# STM32G4.net
KiCad netlist of a schematic drawn in Altium Designer
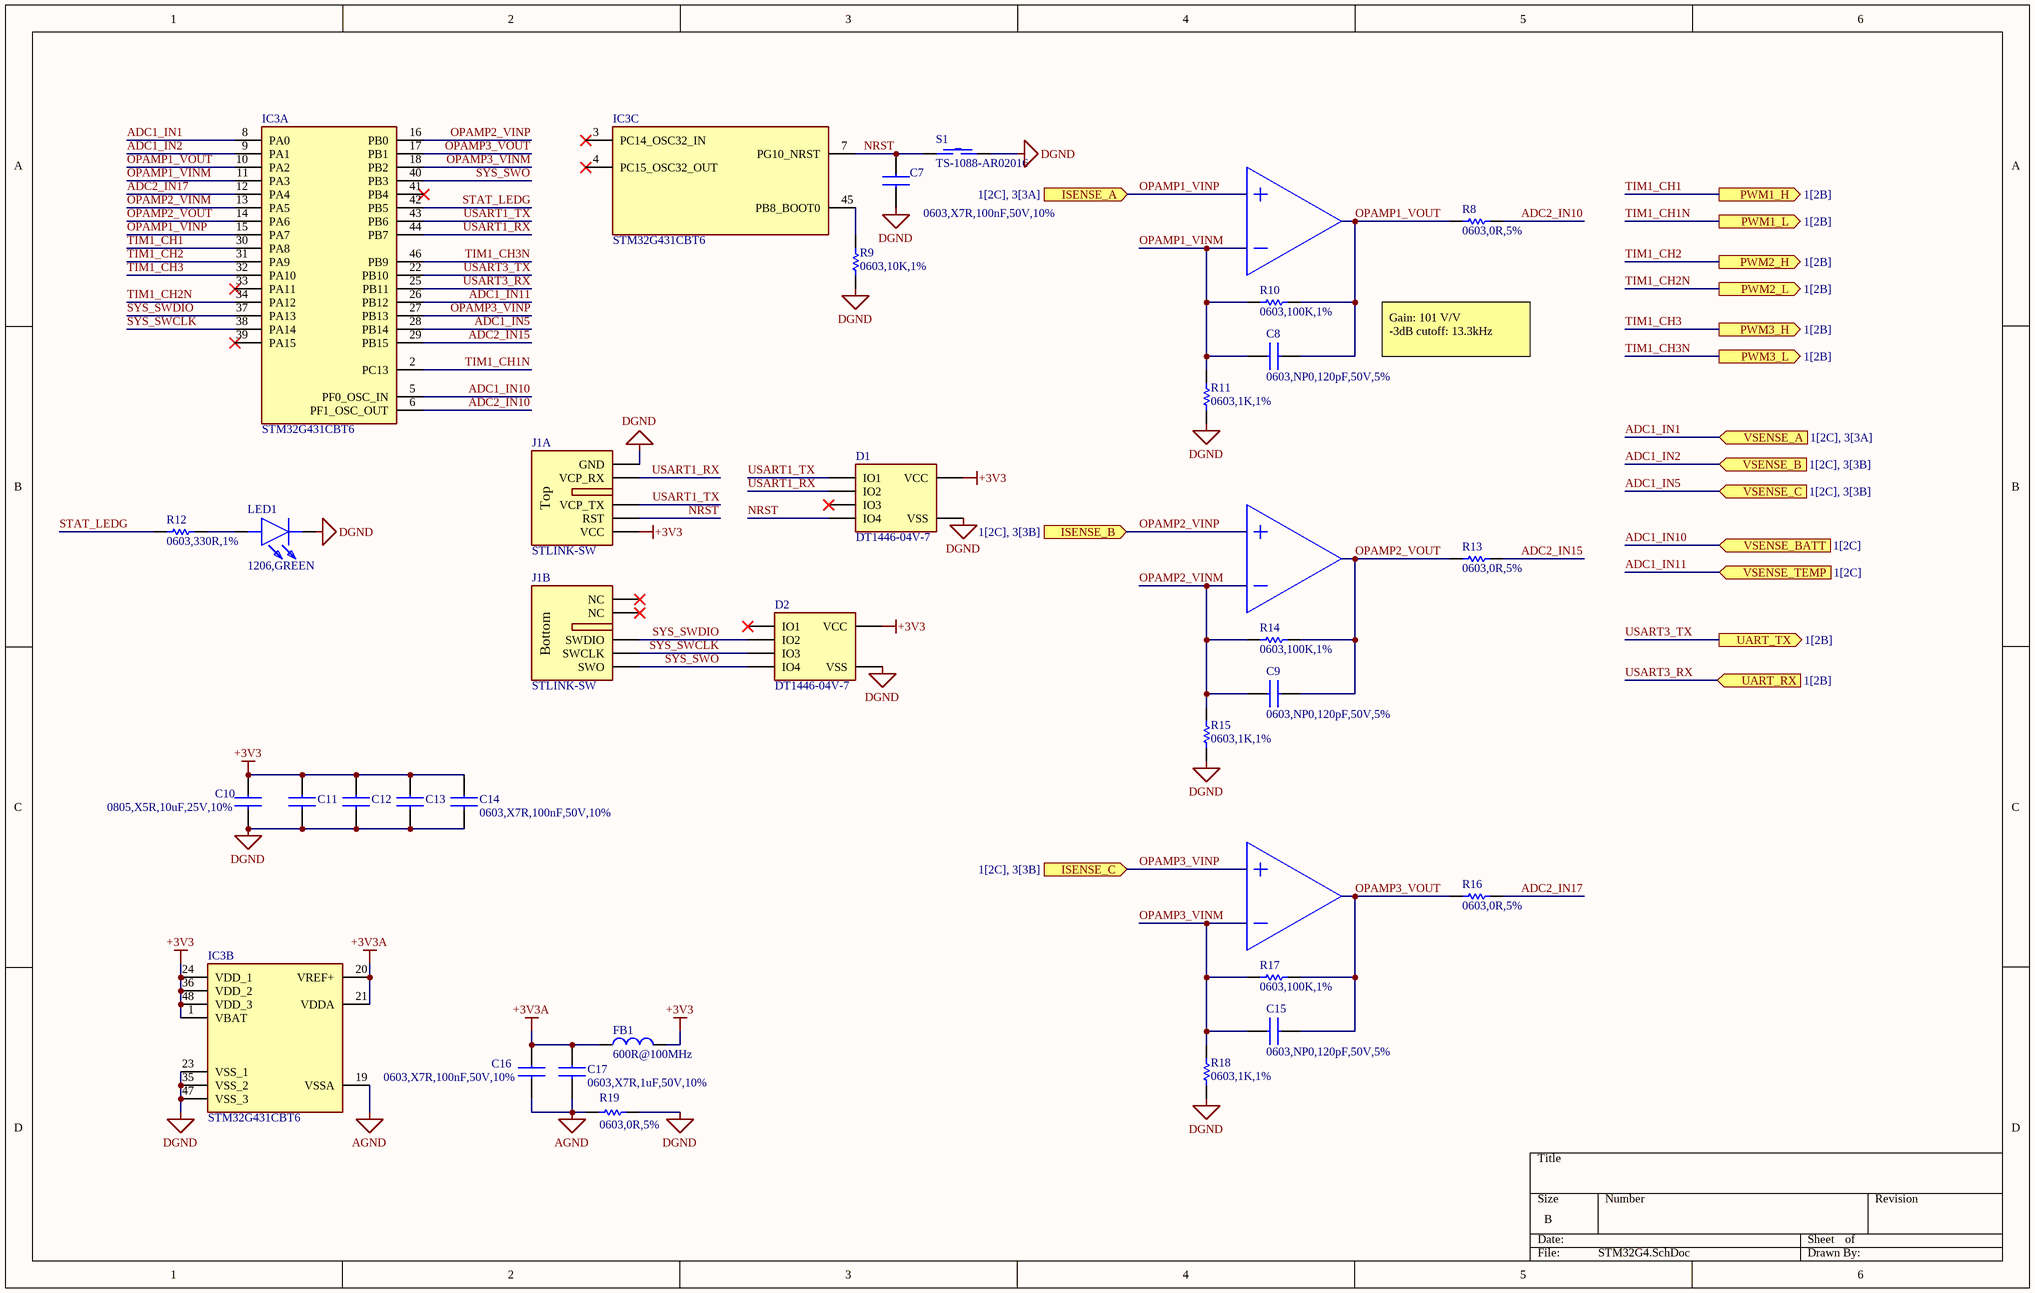
[diagram p0: STM32G4.SchDoc]

(export (version "E")
  (design (tool "Eeschema 10.0.6"))
  (components
    (comp (ref "C7")
      (value "0603,X7R,100nF,50V,10%")
      (footprint "CAPC1608X90N")
      (description "50V 100nF X7R ±10% 0603 Multilayer Ceramic Capacitors MLCC - SMD/SMT ROHS")
      (fields
        (field (name "MANUFACTURER_PART_NUMBER") "CC0603KRX7R9BB104")
        (field (name "MOUSER PART NUMBER") "603-CC603KRX7R9BB104")
      )
      (libsource (lib "ESC") (part "CC0603KRX7R9BB104"))
    )
    (comp (ref "C8")
      (value "0603,NP0,120pF,50V,5%")
      (footprint "CAPC1608X90N")
      (description "50V 120pF NP0 ±5% 0603 Multilayer Ceramic Capacitors MLCC - SMD/SMT ROHS")
      (fields
        (field (name "MANUFACTURER_PART_NUMBER") "CC0603JRNPO9BN121")
        (field (name "MOUSER PART NUMBER") "603-CC603KRX7R9BB104")
      )
      (libsource (lib "ESC") (part "CC0603JRNPO9BN121"))
    )
    (comp (ref "C9")
      (value "0603,NP0,120pF,50V,5%")
      (footprint "CAPC1608X90N")
      (description "50V 120pF NP0 ±5% 0603 Multilayer Ceramic Capacitors MLCC - SMD/SMT ROHS")
      (fields
        (field (name "MANUFACTURER_PART_NUMBER") "CC0603JRNPO9BN121")
        (field (name "MOUSER PART NUMBER") "603-CC603KRX7R9BB104")
      )
      (libsource (lib "ESC") (part "CC0603JRNPO9BN121"))
    )
    (comp (ref "C10")
      (value "0805,X5R,10uF,25V,10%")
      (footprint "CAPC2012X145N")
      (description "10 µF ±10% 25V Ceramic Capacitor X5R 0805 (2012 Metric)")
      (fields
        (field (name "MANUFACTURER_PART_NUMBER") "CC0805KKX5R8BB106")
        (field (name "MOUSER PART NUMBER") "603-CC805KKX5R8BB106")
      )
      (libsource (lib "ESC") (part "CC0805KKX5R8BB106"))
    )
    (comp (ref "C11")
      (value "0603,X7R,100nF,50V,10%")
      (footprint "CAPC1608X90N")
      (description "50V 100nF X7R ±10% 0603 Multilayer Ceramic Capacitors MLCC - SMD/SMT ROHS")
      (fields
        (field (name "MANUFACTURER_PART_NUMBER") "CC0603KRX7R9BB104")
        (field (name "MOUSER PART NUMBER") "603-CC603KRX7R9BB104")
      )
      (libsource (lib "ESC") (part "CC0603KRX7R9BB104"))
    )
    (comp (ref "C12")
      (value "0603,X7R,100nF,50V,10%")
      (footprint "CAPC1608X90N")
      (description "50V 100nF X7R ±10% 0603 Multilayer Ceramic Capacitors MLCC - SMD/SMT ROHS")
      (fields
        (field (name "MANUFACTURER_PART_NUMBER") "CC0603KRX7R9BB104")
        (field (name "MOUSER PART NUMBER") "603-CC603KRX7R9BB104")
      )
      (libsource (lib "ESC") (part "CC0603KRX7R9BB104"))
    )
    (comp (ref "C13")
      (value "0603,X7R,100nF,50V,10%")
      (footprint "CAPC1608X90N")
      (description "50V 100nF X7R ±10% 0603 Multilayer Ceramic Capacitors MLCC - SMD/SMT ROHS")
      (fields
        (field (name "MANUFACTURER_PART_NUMBER") "CC0603KRX7R9BB104")
        (field (name "MOUSER PART NUMBER") "603-CC603KRX7R9BB104")
      )
      (libsource (lib "ESC") (part "CC0603KRX7R9BB104"))
    )
    (comp (ref "C14")
      (value "0603,X7R,100nF,50V,10%")
      (footprint "CAPC1608X90N")
      (description "50V 100nF X7R ±10% 0603 Multilayer Ceramic Capacitors MLCC - SMD/SMT ROHS")
      (fields
        (field (name "MANUFACTURER_PART_NUMBER") "CC0603KRX7R9BB104")
        (field (name "MOUSER PART NUMBER") "603-CC603KRX7R9BB104")
      )
      (libsource (lib "ESC") (part "CC0603KRX7R9BB104"))
    )
    (comp (ref "C15")
      (value "0603,NP0,120pF,50V,5%")
      (footprint "CAPC1608X90N")
      (description "50V 120pF NP0 ±5% 0603 Multilayer Ceramic Capacitors MLCC - SMD/SMT ROHS")
      (fields
        (field (name "MANUFACTURER_PART_NUMBER") "CC0603JRNPO9BN121")
        (field (name "MOUSER PART NUMBER") "603-CC603KRX7R9BB104")
      )
      (libsource (lib "ESC") (part "CC0603JRNPO9BN121"))
    )
    (comp (ref "C16")
      (value "0603,X7R,100nF,50V,10%")
      (footprint "CAPC1608X90N")
      (description "50V 100nF X7R ±10% 0603 Multilayer Ceramic Capacitors MLCC - SMD/SMT ROHS")
      (fields
        (field (name "MANUFACTURER_PART_NUMBER") "CC0603KRX7R9BB104")
        (field (name "MOUSER PART NUMBER") "603-CC603KRX7R9BB104")
      )
      (libsource (lib "ESC") (part "CC0603KRX7R9BB104"))
    )
    (comp (ref "C17")
      (value "0603,X7R,1uF,50V,10%")
      (footprint "CAPC1608X90N")
      (description "50V 1uF X7R ±10% 0603 Multilayer Ceramic Capacitors MLCC - SMD/SMT ROHS")
      (fields
        (field (name "MANUFACTURER_PART_NUMBER") "CC0603KRX7R9BB105")
        (field (name "MOUSER PART NUMBER") "603-CC603KRX7R9BB105")
      )
      (libsource (lib "ESC") (part "CC0603KRX7R9BB105"))
    )
    (comp (ref "D1")
      (value "DT1446-04V-7")
      (footprint "SOTFL50P162X60-6N")
      (description "8.5V Clamp 4.7A (8/20µs) Ipp Tvs Diode Surface Mount SOT-563")
      (fields (field (name "MOUSER PART NUMBER") "621-DT1446-04V-7") (field (name "LCSC PART #") "C460066"))
      (libsource (lib "ESC") (part "DT1446-04V-7"))
    )
    (comp (ref "D2")
      (value "DT1446-04V-7")
      (footprint "SOTFL50P162X60-6N")
      (description "8.5V Clamp 4.7A (8/20µs) Ipp Tvs Diode Surface Mount SOT-563")
      (fields (field (name "MOUSER PART NUMBER") "621-DT1446-04V-7") (field (name "LCSC PART #") "C460066"))
      (libsource (lib "ESC") (part "DT1446-04V-7"))
    )
    (comp (ref "FB1")
      (value "600R@100MHz")
      (footprint "L0603")
      (description "380mΩ ±25% 600Ω@100MHz 0603 Ferrite Beads ROHS")
      (fields (field (name "LCSC PART #") "C19330"))
      (libsource (lib "ESC") (part "BLM18AG601SN1D"))
    )
    (comp (ref "IC3")
      (value "STM32G431CBT6")
      (footprint "QFP50P900X900X160-48N")
      (fields (field (name "MOUSER PART NUMBER") "511-STM32G431CBT6") (field (name "LCSC PART #") "C529355"))
      (libsource (lib "ESC") (part "STM32G431CBT6"))
    )
    (comp (ref "J1")
      (value "STLINK-SW")
      (footprint "Valkyrie ESC:009159010061911")
      (description "SSL Connector 10 Position Adapter, Bridge Board to Board - Card Edge 0.079\" (2.00mm)")
      (libsource (lib "ESC") (part "STLINK-SW"))
    )
    (comp (ref "LED1")
      (value "1206,GREEN")
      (footprint "LEDC3216X120N")
      (fields
        (field (name "MANUFACTURER_PART_NUMBER") "LTST-C150KGKT")
        (field (name "MOUSER PART NUMBER") "859-LTST-C150KGKT")
        (field (name "LCSC PART #") "C125085")
      )
      (libsource (lib "ESC") (part "LTST-C150KGKT"))
    )
    (comp (ref "R8")
      (value "0603,0R,5%")
      (footprint "RESC1608X55N")
      (description "100mW Thick Film Resistor 75V ±5% 0Ω 0603 Chip Resistor - Surface Mount ROHS")
      (fields
        (field (name "MANUFACTURER_PART_NUMBER") "RC0603JR-070RL")
        (field (name "LCSC PART #") "C95177")
      )
      (libsource (lib "ESC") (part "RC0603JR-070RL"))
    )
    (comp (ref "R9")
      (value "0603,10K,1%")
      (footprint "RESC1608X55N")
      (description "100mW 10kΩ 75V ±100ppm/℃ Thick Film Resistor ±1% 0603 Chip Resistor - Surface Mount RoHS")
      (fields
        (field (name "MANUFACTURER_PART_NUMBER") "RC0603FR-0710KL")
        (field (name "LCSC PART #") "C98220")
      )
      (libsource (lib "ESC") (part "RC0603FR-0710KL"))
    )
    (comp (ref "R10")
      (value "0603,100K,1%")
      (footprint "RESC1608X55N")
      (description "100mW Thick Film Resistor 75V ±100ppm/℃ ±1% 100kΩ 0603 Chip Resistor - Surface Mount ROHS")
      (fields
        (field (name "MANUFACTURER_PART_NUMBER") "RC0603FR-07100KL")
        (field (name "LCSC PART #") "C14675")
      )
      (libsource (lib "ESC") (part "RC0603FR-07100KL"))
    )
    (comp (ref "R11")
      (value "0603,1K,1%")
      (footprint "RESC1608X55N")
      (description "100mW Thick Film Resistor 75V ±100ppm/℃ ±1% 1kΩ 0603 Chip Resistor - Surface Mount ROHS")
      (fields
        (field (name "MANUFACTURER_PART_NUMBER") "RC0603FR-071KL")
        (field (name "LCSC PART #") "C22548")
      )
      (libsource (lib "ESC") (part "RC0603FR-071KL"))
    )
    (comp (ref "R12")
      (value "0603,330R,1%")
      (footprint "RESC1608X55N")
      (description "100mW 330Ω 75V ±100ppm/℃ Thick Film Resistor ±1% 0603 Chip Resistor - Surface Mount RoHS")
      (fields
        (field (name "MANUFACTURER_PART_NUMBER") "RC0603FR-07330RL")
        (field (name "LCSC PART #") "C105881")
      )
      (libsource (lib "ESC") (part "RC0603FR-07330RL"))
    )
    (comp (ref "R13")
      (value "0603,0R,5%")
      (footprint "RESC1608X55N")
      (description "100mW Thick Film Resistor 75V ±5% 0Ω 0603 Chip Resistor - Surface Mount ROHS")
      (fields
        (field (name "MANUFACTURER_PART_NUMBER") "RC0603JR-070RL")
        (field (name "LCSC PART #") "C95177")
      )
      (libsource (lib "ESC") (part "RC0603JR-070RL"))
    )
    (comp (ref "R14")
      (value "0603,100K,1%")
      (footprint "RESC1608X55N")
      (description "100mW Thick Film Resistor 75V ±100ppm/℃ ±1% 100kΩ 0603 Chip Resistor - Surface Mount ROHS")
      (fields
        (field (name "MANUFACTURER_PART_NUMBER") "RC0603FR-07100KL")
        (field (name "LCSC PART #") "C14675")
      )
      (libsource (lib "ESC") (part "RC0603FR-07100KL"))
    )
    (comp (ref "R15")
      (value "0603,1K,1%")
      (footprint "RESC1608X55N")
      (description "100mW Thick Film Resistor 75V ±100ppm/℃ ±1% 1kΩ 0603 Chip Resistor - Surface Mount ROHS")
      (fields
        (field (name "MANUFACTURER_PART_NUMBER") "RC0603FR-071KL")
        (field (name "LCSC PART #") "C22548")
      )
      (libsource (lib "ESC") (part "RC0603FR-071KL"))
    )
    (comp (ref "R16")
      (value "0603,0R,5%")
      (footprint "RESC1608X55N")
      (description "100mW Thick Film Resistor 75V ±5% 0Ω 0603 Chip Resistor - Surface Mount ROHS")
      (fields
        (field (name "MANUFACTURER_PART_NUMBER") "RC0603JR-070RL")
        (field (name "LCSC PART #") "C95177")
      )
      (libsource (lib "ESC") (part "RC0603JR-070RL"))
    )
    (comp (ref "R17")
      (value "0603,100K,1%")
      (footprint "RESC1608X55N")
      (description "100mW Thick Film Resistor 75V ±100ppm/℃ ±1% 100kΩ 0603 Chip Resistor - Surface Mount ROHS")
      (fields
        (field (name "MANUFACTURER_PART_NUMBER") "RC0603FR-07100KL")
        (field (name "LCSC PART #") "C14675")
      )
      (libsource (lib "ESC") (part "RC0603FR-07100KL"))
    )
    (comp (ref "R18")
      (value "0603,1K,1%")
      (footprint "RESC1608X55N")
      (description "100mW Thick Film Resistor 75V ±100ppm/℃ ±1% 1kΩ 0603 Chip Resistor - Surface Mount ROHS")
      (fields
        (field (name "MANUFACTURER_PART_NUMBER") "RC0603FR-071KL")
        (field (name "LCSC PART #") "C22548")
      )
      (libsource (lib "ESC") (part "RC0603FR-071KL"))
    )
    (comp (ref "R19")
      (value "0603,0R,5%")
      (footprint "RESC1608X55N")
      (description "100mW Thick Film Resistor 75V ±5% 0Ω 0603 Chip Resistor - Surface Mount ROHS")
      (fields
        (field (name "MANUFACTURER_PART_NUMBER") "RC0603JR-070RL")
        (field (name "LCSC PART #") "C95177")
      )
      (libsource (lib "ESC") (part "RC0603JR-070RL"))
    )
    (comp (ref "S1")
      (value "TS-1088-AR02016")
      (footprint "SW-SMD_L3.9-W3.0-P4.45")
      (fields (field (name "LCSC PART #") "C720477"))
      (libsource (lib "ESC") (part "TS-1088-AR02016"))
    )
  )
  (nets
    (net (code "1") (name "+3V3") (class "Default")
      (node (ref "C10") (pin "2") (pinfunction "2_2") (pintype "passive"))
      (node (ref "C11") (pin "2") (pinfunction "2_2") (pintype "passive"))
      (node (ref "C12") (pin "2") (pinfunction "2_2") (pintype "passive"))
      (node (ref "C13") (pin "2") (pinfunction "2_2") (pintype "passive"))
      (node (ref "C14") (pin "2") (pinfunction "2_2") (pintype "passive"))
      (node (ref "D1") (pin "5") (pinfunction "VCC_5") (pintype "passive"))
      (node (ref "D2") (pin "5") (pinfunction "VCC_5") (pintype "passive"))
      (node (ref "FB1") (pin "2") (pinfunction "2_2") (pintype "passive"))
      (node (ref "IC3") (pin "1") (pinfunction "VBAT_1") (pintype "passive"))
      (node (ref "IC3") (pin "24") (pinfunction "VDD_1_24") (pintype "passive"))
      (node (ref "IC3") (pin "36") (pinfunction "VDD_2_36") (pintype "passive"))
      (node (ref "IC3") (pin "48") (pinfunction "VDD_3_48") (pintype "passive"))
      (node (ref "J1") (pin "5") (pinfunction "VCC_5") (pintype "passive"))
    )
    (net (code "2") (name "+3V3A") (class "Default")
      (node (ref "C16") (pin "2") (pinfunction "2_2") (pintype "passive"))
      (node (ref "C17") (pin "2") (pinfunction "2_2") (pintype "passive"))
      (node (ref "FB1") (pin "1") (pinfunction "1_1") (pintype "passive"))
      (node (ref "IC3") (pin "20") (pinfunction "VREF+_20") (pintype "passive"))
      (node (ref "IC3") (pin "21") (pinfunction "VDDA_21") (pintype "passive"))
    )
    (net (code "3") (name "/ADC1_IN1") (class "Default")
      (node (ref "IC3") (pin "8") (pinfunction "PA0_8") (pintype "passive"))
    )
    (net (code "4") (name "/ADC1_IN2") (class "Default")
      (node (ref "IC3") (pin "9") (pinfunction "PA1_9") (pintype "passive"))
    )
    (net (code "5") (name "/ADC1_IN5") (class "Default")
      (node (ref "IC3") (pin "28") (pinfunction "PB14_28") (pintype "passive"))
    )
    (net (code "6") (name "/ADC1_IN10") (class "Default")
      (node (ref "IC3") (pin "5") (pinfunction "PF0_OSC_IN_5") (pintype "passive"))
    )
    (net (code "7") (name "/ADC1_IN11") (class "Default")
      (node (ref "IC3") (pin "26") (pinfunction "PB12_26") (pintype "passive"))
    )
    (net (code "8") (name "/ADC2_IN10") (class "Default")
      (node (ref "IC3") (pin "6") (pinfunction "PF1_OSC_OUT_6") (pintype "passive"))
      (node (ref "R8") (pin "2") (pinfunction "2_2") (pintype "passive"))
    )
    (net (code "9") (name "/ADC2_IN15") (class "Default")
      (node (ref "IC3") (pin "29") (pinfunction "PB15_29") (pintype "passive"))
      (node (ref "R13") (pin "2") (pinfunction "2_2") (pintype "passive"))
    )
    (net (code "10") (name "/ADC2_IN17") (class "Default")
      (node (ref "IC3") (pin "12") (pinfunction "PA4_12") (pintype "passive"))
      (node (ref "R16") (pin "2") (pinfunction "2_2") (pintype "passive"))
    )
    (net (code "11") (name "/NRST") (class "Default")
      (node (ref "C7") (pin "2") (pinfunction "2_2") (pintype "passive"))
      (node (ref "D1") (pin "6") (pinfunction "IO4_6") (pintype "passive"))
      (node (ref "IC3") (pin "7") (pinfunction "PG10_NRST_7") (pintype "passive"))
      (node (ref "J1") (pin "4") (pinfunction "RST_4") (pintype "passive"))
      (node (ref "S1") (pin "2") (pinfunction "2_2") (pintype "passive"))
    )
    (net (code "12") (name "/OPAMP1_VINM") (class "Default")
      (node (ref "C8") (pin "1") (pinfunction "1_1") (pintype "passive"))
      (node (ref "IC3") (pin "11") (pinfunction "PA3_11") (pintype "passive"))
      (node (ref "R10") (pin "1") (pinfunction "1_1") (pintype "passive"))
      (node (ref "R11") (pin "2") (pinfunction "2_2") (pintype "passive"))
    )
    (net (code "13") (name "/OPAMP1_VINP") (class "Default")
      (node (ref "IC3") (pin "15") (pinfunction "PA7_15") (pintype "passive"))
    )
    (net (code "14") (name "/OPAMP1_VOUT") (class "Default")
      (node (ref "C8") (pin "2") (pinfunction "2_2") (pintype "passive"))
      (node (ref "IC3") (pin "10") (pinfunction "PA2_10") (pintype "passive"))
      (node (ref "R10") (pin "2") (pinfunction "2_2") (pintype "passive"))
      (node (ref "R8") (pin "1") (pinfunction "1_1") (pintype "passive"))
    )
    (net (code "15") (name "/OPAMP2_VINM") (class "Default")
      (node (ref "C9") (pin "1") (pinfunction "1_1") (pintype "passive"))
      (node (ref "IC3") (pin "13") (pinfunction "PA5_13") (pintype "passive"))
      (node (ref "R14") (pin "1") (pinfunction "1_1") (pintype "passive"))
      (node (ref "R15") (pin "2") (pinfunction "2_2") (pintype "passive"))
    )
    (net (code "16") (name "/OPAMP2_VINP") (class "Default")
      (node (ref "IC3") (pin "16") (pinfunction "PB0_16") (pintype "passive"))
    )
    (net (code "17") (name "/OPAMP2_VOUT") (class "Default")
      (node (ref "C9") (pin "2") (pinfunction "2_2") (pintype "passive"))
      (node (ref "IC3") (pin "14") (pinfunction "PA6_14") (pintype "passive"))
      (node (ref "R13") (pin "1") (pinfunction "1_1") (pintype "passive"))
      (node (ref "R14") (pin "2") (pinfunction "2_2") (pintype "passive"))
    )
    (net (code "18") (name "/OPAMP3_VINM") (class "Default")
      (node (ref "C15") (pin "1") (pinfunction "1_1") (pintype "passive"))
      (node (ref "IC3") (pin "18") (pinfunction "PB2_18") (pintype "passive"))
      (node (ref "R17") (pin "1") (pinfunction "1_1") (pintype "passive"))
      (node (ref "R18") (pin "2") (pinfunction "2_2") (pintype "passive"))
    )
    (net (code "19") (name "/OPAMP3_VINP") (class "Default")
      (node (ref "IC3") (pin "27") (pinfunction "PB13_27") (pintype "passive"))
    )
    (net (code "20") (name "/OPAMP3_VOUT") (class "Default")
      (node (ref "C15") (pin "2") (pinfunction "2_2") (pintype "passive"))
      (node (ref "IC3") (pin "17") (pinfunction "PB1_17") (pintype "passive"))
      (node (ref "R16") (pin "1") (pinfunction "1_1") (pintype "passive"))
      (node (ref "R17") (pin "2") (pinfunction "2_2") (pintype "passive"))
    )
    (net (code "21") (name "/STAT_LEDG") (class "Default")
      (node (ref "IC3") (pin "42") (pinfunction "PB5_42") (pintype "passive"))
      (node (ref "R12") (pin "1") (pinfunction "1_1") (pintype "passive"))
    )
    (net (code "22") (name "/SYS_SWCLK") (class "Default")
      (node (ref "D2") (pin "4") (pinfunction "IO3_4") (pintype "passive"))
      (node (ref "IC3") (pin "38") (pinfunction "PA14_38") (pintype "passive"))
      (node (ref "J1") (pin "9") (pinfunction "SWCLK_9") (pintype "passive"))
    )
    (net (code "23") (name "/SYS_SWDIO") (class "Default")
      (node (ref "D2") (pin "3") (pinfunction "IO2_3") (pintype "passive"))
      (node (ref "IC3") (pin "37") (pinfunction "PA13_37") (pintype "passive"))
      (node (ref "J1") (pin "8") (pinfunction "SWDIO_8") (pintype "passive"))
    )
    (net (code "24") (name "/SYS_SWO") (class "Default")
      (node (ref "D2") (pin "6") (pinfunction "IO4_6") (pintype "passive"))
      (node (ref "IC3") (pin "40") (pinfunction "PB3_40") (pintype "passive"))
      (node (ref "J1") (pin "10") (pinfunction "SWO_10") (pintype "passive"))
    )
    (net (code "25") (name "/TIM1_CH1") (class "Default")
      (node (ref "IC3") (pin "30") (pinfunction "PA8_30") (pintype "passive"))
    )
    (net (code "26") (name "/TIM1_CH1N") (class "Default")
      (node (ref "IC3") (pin "2") (pinfunction "PC13_2") (pintype "passive"))
    )
    (net (code "27") (name "/TIM1_CH2") (class "Default")
      (node (ref "IC3") (pin "31") (pinfunction "PA9_31") (pintype "passive"))
    )
    (net (code "28") (name "/TIM1_CH2N") (class "Default")
      (node (ref "IC3") (pin "34") (pinfunction "PA12_34") (pintype "passive"))
    )
    (net (code "29") (name "/TIM1_CH3") (class "Default")
      (node (ref "IC3") (pin "32") (pinfunction "PA10_32") (pintype "passive"))
    )
    (net (code "30") (name "/TIM1_CH3N") (class "Default")
      (node (ref "IC3") (pin "46") (pinfunction "PB9_46") (pintype "passive"))
    )
    (net (code "31") (name "/USART1_RX") (class "Default")
      (node (ref "D1") (pin "3") (pinfunction "IO2_3") (pintype "passive"))
      (node (ref "IC3") (pin "44") (pinfunction "PB7_44") (pintype "passive"))
      (node (ref "J1") (pin "2") (pinfunction "VCP_RX_2") (pintype "passive"))
    )
    (net (code "32") (name "/USART1_TX") (class "Default")
      (node (ref "D1") (pin "1") (pinfunction "IO1_1") (pintype "passive"))
      (node (ref "IC3") (pin "43") (pinfunction "PB6_43") (pintype "passive"))
      (node (ref "J1") (pin "3") (pinfunction "VCP_TX_3") (pintype "passive"))
    )
    (net (code "33") (name "/USART3_RX") (class "Default")
      (node (ref "IC3") (pin "25") (pinfunction "PB11_25") (pintype "passive"))
    )
    (net (code "34") (name "/USART3_TX") (class "Default")
      (node (ref "IC3") (pin "22") (pinfunction "PB10_22") (pintype "passive"))
    )
    (net (code "35") (name "AGND") (class "Default")
      (node (ref "C16") (pin "1") (pinfunction "1_1") (pintype "passive"))
      (node (ref "C17") (pin "1") (pinfunction "1_1") (pintype "passive"))
      (node (ref "IC3") (pin "19") (pinfunction "VSSA_19") (pintype "passive"))
      (node (ref "R19") (pin "1") (pinfunction "1_1") (pintype "passive"))
    )
    (net (code "36") (name "DGND") (class "Default")
      (node (ref "C10") (pin "1") (pinfunction "1_1") (pintype "passive"))
      (node (ref "C11") (pin "1") (pinfunction "1_1") (pintype "passive"))
      (node (ref "C12") (pin "1") (pinfunction "1_1") (pintype "passive"))
      (node (ref "C13") (pin "1") (pinfunction "1_1") (pintype "passive"))
      (node (ref "C14") (pin "1") (pinfunction "1_1") (pintype "passive"))
      (node (ref "C7") (pin "1") (pinfunction "1_1") (pintype "passive"))
      (node (ref "D1") (pin "2") (pinfunction "VSS_2") (pintype "passive"))
      (node (ref "D2") (pin "2") (pinfunction "VSS_2") (pintype "passive"))
      (node (ref "IC3") (pin "23") (pinfunction "VSS_1_23") (pintype "passive"))
      (node (ref "IC3") (pin "35") (pinfunction "VSS_2_35") (pintype "passive"))
      (node (ref "IC3") (pin "47") (pinfunction "VSS_3_47") (pintype "passive"))
      (node (ref "J1") (pin "1") (pinfunction "GND_1") (pintype "passive"))
      (node (ref "LED1") (pin "1") (pinfunction "K_1") (pintype "passive"))
      (node (ref "R11") (pin "1") (pinfunction "1_1") (pintype "passive"))
      (node (ref "R15") (pin "1") (pinfunction "1_1") (pintype "passive"))
      (node (ref "R18") (pin "1") (pinfunction "1_1") (pintype "passive"))
      (node (ref "R19") (pin "2") (pinfunction "2_2") (pintype "passive"))
      (node (ref "R9") (pin "1") (pinfunction "1_1") (pintype "passive"))
      (node (ref "S1") (pin "1") (pinfunction "1_1") (pintype "passive"))
    )
    (net (code "37") (name "Net-(IC3C-PB8_BOOT0)") (class "Default")
      (node (ref "IC3") (pin "45") (pinfunction "PB8_BOOT0_45") (pintype "passive"))
      (node (ref "R9") (pin "2") (pinfunction "2_2") (pintype "passive"))
    )
    (net (code "38") (name "Net-(LED1-A)") (class "Default")
      (node (ref "LED1") (pin "2") (pinfunction "A_2") (pintype "passive"))
      (node (ref "R12") (pin "2") (pinfunction "2_2") (pintype "passive"))
    )
    (net (code "39") (name "unconnected-(D1-IO3-Pad4)") (class "Default")
      (node (ref "D1") (pin "4") (pinfunction "IO3_4") (pintype "passive+no_connect"))
    )
    (net (code "40") (name "unconnected-(D2-IO1-Pad1)") (class "Default")
      (node (ref "D2") (pin "1") (pinfunction "IO1_1") (pintype "passive+no_connect"))
    )
    (net (code "41") (name "unconnected-(IC3A-PA11-Pad33)") (class "Default")
      (node (ref "IC3") (pin "33") (pinfunction "PA11_33") (pintype "passive+no_connect"))
    )
    (net (code "42") (name "unconnected-(IC3A-PA15-Pad39)") (class "Default")
      (node (ref "IC3") (pin "39") (pinfunction "PA15_39") (pintype "passive+no_connect"))
    )
    (net (code "43") (name "unconnected-(IC3A-PB4-Pad41)") (class "Default")
      (node (ref "IC3") (pin "41") (pinfunction "PB4_41") (pintype "passive+no_connect"))
    )
    (net (code "44") (name "unconnected-(IC3C-PC14_OSC32_IN-Pad3)") (class "Default")
      (node (ref "IC3") (pin "3") (pinfunction "PC14_OSC32_IN_3") (pintype "passive+no_connect"))
    )
    (net (code "45") (name "unconnected-(IC3C-PC15_OSC32_OUT-Pad4)") (class "Default")
      (node (ref "IC3") (pin "4") (pinfunction "PC15_OSC32_OUT_4") (pintype "passive+no_connect"))
    )
    (net (code "46") (name "unconnected-(J1B-NC-Pad6)") (class "Default")
      (node (ref "J1") (pin "6") (pinfunction "NC_6") (pintype "passive+no_connect"))
    )
    (net (code "47") (name "unconnected-(J1B-NC-Pad7)") (class "Default")
      (node (ref "J1") (pin "7") (pinfunction "NC_7") (pintype "passive+no_connect"))
    )
  )
)
